# P18_CONNECT_DDR1.net
KiCad netlist of a schematic drawn in Altium Designer
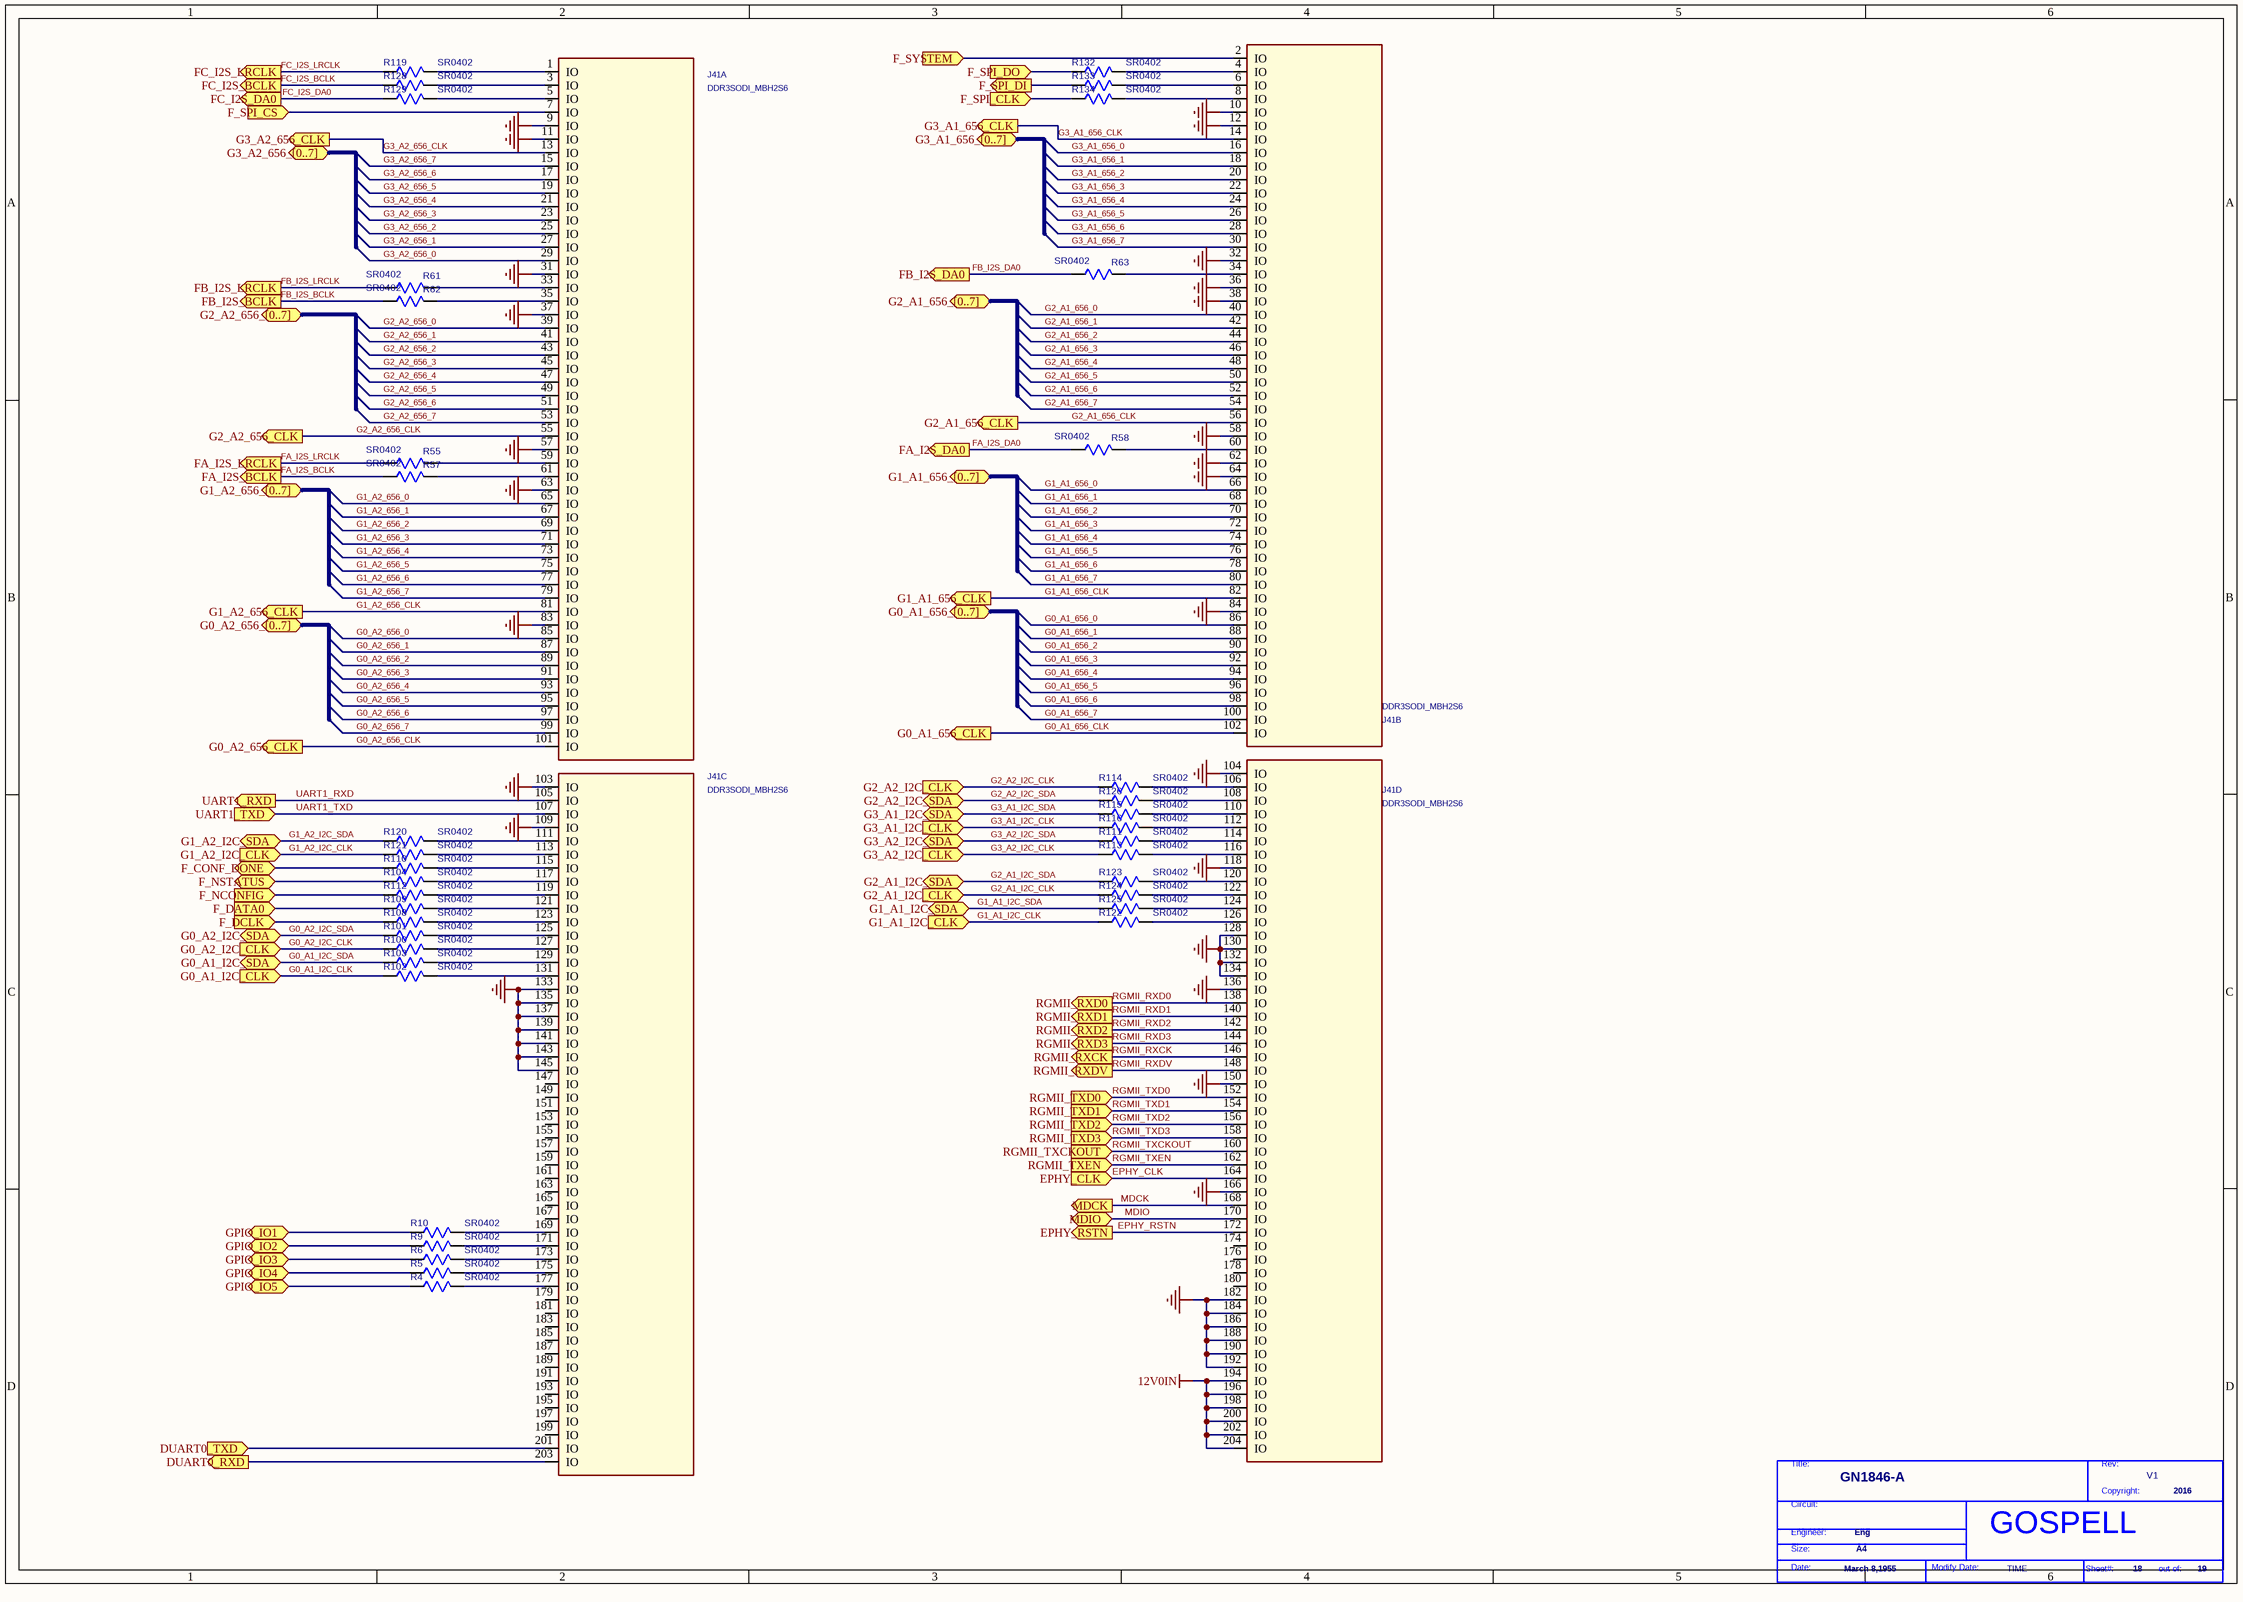
[diagram p0: P18 CONNECT DDR1.SchDoc]

(export (version "E")
  (design (tool "Eeschema 10.0.6"))
  (components
    (comp (ref "J41") (value "DDR3SODI_MBH2S6") (libsource (lib "*") (part "DDRSD_MB")))
    (comp (ref "R4") (value "SR0402") (libsource (lib "*") (part "R_1")))
    (comp (ref "R5") (value "SR0402") (libsource (lib "*") (part "R_1")))
    (comp (ref "R6") (value "SR0402") (libsource (lib "*") (part "R_1")))
    (comp (ref "R9") (value "SR0402") (libsource (lib "*") (part "R_1")))
    (comp (ref "R10") (value "SR0402") (libsource (lib "*") (part "R_1")))
    (comp (ref "R55") (value "SR0402") (libsource (lib "*") (part "R_1")))
    (comp (ref "R57") (value "SR0402") (libsource (lib "*") (part "R_1")))
    (comp (ref "R58") (value "SR0402") (libsource (lib "*") (part "R_1")))
    (comp (ref "R61") (value "SR0402") (libsource (lib "*") (part "R_1")))
    (comp (ref "R62") (value "SR0402") (libsource (lib "*") (part "R_1")))
    (comp (ref "R63") (value "SR0402") (libsource (lib "*") (part "R_1")))
    (comp (ref "R100") (value "SR0402") (libsource (lib "*") (part "R_1")))
    (comp (ref "R101") (value "SR0402") (libsource (lib "*") (part "R_1")))
    (comp (ref "R102") (value "SR0402") (libsource (lib "*") (part "R_1")))
    (comp (ref "R103") (value "SR0402") (libsource (lib "*") (part "R_1")))
    (comp (ref "R104") (value "SR0402") (libsource (lib "*") (part "R_1")))
    (comp (ref "R108") (value "SR0402") (libsource (lib "*") (part "R_1")))
    (comp (ref "R109") (value "SR0402") (libsource (lib "*") (part "R_1")))
    (comp (ref "R110") (value "SR0402") (libsource (lib "*") (part "R_1")))
    (comp (ref "R111") (value "SR0402") (libsource (lib "*") (part "R_1")))
    (comp (ref "R112") (value "SR0402") (libsource (lib "*") (part "R_1")))
    (comp (ref "R113") (value "SR0402") (libsource (lib "*") (part "R_1")))
    (comp (ref "R114") (value "SR0402") (libsource (lib "*") (part "R_1")))
    (comp (ref "R115") (value "SR0402") (libsource (lib "*") (part "R_1")))
    (comp (ref "R116") (value "SR0402") (libsource (lib "*") (part "R_1")))
    (comp (ref "R119") (value "SR0402") (libsource (lib "*") (part "R_1")))
    (comp (ref "R120") (value "SR0402") (libsource (lib "*") (part "R_1")))
    (comp (ref "R121") (value "SR0402") (libsource (lib "*") (part "R_1")))
    (comp (ref "R122") (value "SR0402") (libsource (lib "*") (part "R_1")))
    (comp (ref "R123") (value "SR0402") (libsource (lib "*") (part "R_1")))
    (comp (ref "R124") (value "SR0402") (libsource (lib "*") (part "R_1")))
    (comp (ref "R125") (value "SR0402") (libsource (lib "*") (part "R_1")))
    (comp (ref "R126") (value "SR0402") (libsource (lib "*") (part "R_1")))
    (comp (ref "R128") (value "SR0402") (libsource (lib "*") (part "R_1")))
    (comp (ref "R129") (value "SR0402") (libsource (lib "*") (part "R_1")))
    (comp (ref "R132") (value "SR0402") (libsource (lib "*") (part "R_1")))
    (comp (ref "R133") (value "SR0402") (libsource (lib "*") (part "R_1")))
    (comp (ref "R134") (value "SR0402") (libsource (lib "*") (part "R_1")))
  )
  (nets
    (net (code "1") (name "/DUART0_RXD") (class "Default")
      (node (ref "J41") (pin "203") (pinfunction "IO_203") (pintype "passive"))
    )
    (net (code "2") (name "/DUART0_TXD") (class "Default")
      (node (ref "J41") (pin "201") (pinfunction "IO_201") (pintype "passive"))
    )
    (net (code "3") (name "/EPHY_CLK") (class "Default")
      (node (ref "J41") (pin "164") (pinfunction "IO_164") (pintype "passive"))
    )
    (net (code "4") (name "/EPHY_RSTN") (class "Default")
      (node (ref "J41") (pin "172") (pinfunction "IO_172") (pintype "passive"))
    )
    (net (code "5") (name "/FA_I2S_BCLK") (class "Default")
      (node (ref "R57") (pin "2") (pinfunction "B_2") (pintype "passive"))
    )
    (net (code "6") (name "/FA_I2S_DA0") (class "Default")
      (node (ref "R58") (pin "2") (pinfunction "B_2") (pintype "passive"))
    )
    (net (code "7") (name "/FA_I2S_LRCLK") (class "Default")
      (node (ref "R55") (pin "2") (pinfunction "B_2") (pintype "passive"))
    )
    (net (code "8") (name "/FB_I2S_BCLK") (class "Default")
      (node (ref "R62") (pin "2") (pinfunction "B_2") (pintype "passive"))
    )
    (net (code "9") (name "/FB_I2S_DA0") (class "Default")
      (node (ref "R63") (pin "2") (pinfunction "B_2") (pintype "passive"))
    )
    (net (code "10") (name "/FB_I2S_LRCLK") (class "Default")
      (node (ref "R61") (pin "2") (pinfunction "B_2") (pintype "passive"))
    )
    (net (code "11") (name "/FC_I2S_BCLK") (class "Default")
      (node (ref "R128") (pin "1") (pinfunction "A_1") (pintype "passive"))
    )
    (net (code "12") (name "/FC_I2S_DA0") (class "Default")
      (node (ref "R129") (pin "1") (pinfunction "A_1") (pintype "passive"))
    )
    (net (code "13") (name "/FC_I2S_LRCLK") (class "Default")
      (node (ref "R119") (pin "1") (pinfunction "A_1") (pintype "passive"))
    )
    (net (code "14") (name "/F_CONF_DONE") (class "Default")
      (node (ref "R110") (pin "1") (pinfunction "A_1") (pintype "passive"))
    )
    (net (code "15") (name "/F_DATA0") (class "Default")
      (node (ref "R109") (pin "1") (pinfunction "A_1") (pintype "passive"))
    )
    (net (code "16") (name "/F_DCLK") (class "Default")
      (node (ref "R108") (pin "1") (pinfunction "A_1") (pintype "passive"))
    )
    (net (code "17") (name "/F_NCONFIG") (class "Default")
      (node (ref "R112") (pin "1") (pinfunction "A_1") (pintype "passive"))
    )
    (net (code "18") (name "/F_NSTATUS") (class "Default")
      (node (ref "R104") (pin "1") (pinfunction "A_1") (pintype "passive"))
    )
    (net (code "19") (name "/F_SPI_CLK") (class "Default")
      (node (ref "R134") (pin "1") (pinfunction "A_1") (pintype "passive"))
    )
    (net (code "20") (name "/F_SPI_CS") (class "Default")
      (node (ref "J41") (pin "7") (pinfunction "IO_7") (pintype "passive"))
    )
    (net (code "21") (name "/F_SPI_DI") (class "Default")
      (node (ref "R133") (pin "1") (pinfunction "A_1") (pintype "passive"))
    )
    (net (code "22") (name "/F_SPI_DO") (class "Default")
      (node (ref "R132") (pin "1") (pinfunction "A_1") (pintype "passive"))
    )
    (net (code "23") (name "/F_SYSTEM") (class "Default")
      (node (ref "J41") (pin "2") (pinfunction "IO_2") (pintype "passive"))
    )
    (net (code "24") (name "/G0_A1_656_0") (class "Default")
      (node (ref "J41") (pin "86") (pinfunction "IO_86") (pintype "passive"))
    )
    (net (code "25") (name "/G0_A1_656_1") (class "Default")
      (node (ref "J41") (pin "88") (pinfunction "IO_88") (pintype "passive"))
    )
    (net (code "26") (name "/G0_A1_656_2") (class "Default")
      (node (ref "J41") (pin "90") (pinfunction "IO_90") (pintype "passive"))
    )
    (net (code "27") (name "/G0_A1_656_3") (class "Default")
      (node (ref "J41") (pin "92") (pinfunction "IO_92") (pintype "passive"))
    )
    (net (code "28") (name "/G0_A1_656_4") (class "Default")
      (node (ref "J41") (pin "94") (pinfunction "IO_94") (pintype "passive"))
    )
    (net (code "29") (name "/G0_A1_656_5") (class "Default")
      (node (ref "J41") (pin "96") (pinfunction "IO_96") (pintype "passive"))
    )
    (net (code "30") (name "/G0_A1_656_6") (class "Default")
      (node (ref "J41") (pin "98") (pinfunction "IO_98") (pintype "passive"))
    )
    (net (code "31") (name "/G0_A1_656_7") (class "Default")
      (node (ref "J41") (pin "100") (pinfunction "IO_100") (pintype "passive"))
    )
    (net (code "32") (name "/G0_A1_656_CLK") (class "Default")
      (node (ref "J41") (pin "102") (pinfunction "IO_102") (pintype "passive"))
    )
    (net (code "34") (name "/G0_A1_I2C_CLK") (class "Default")
      (node (ref "R102") (pin "1") (pinfunction "A_1") (pintype "passive"))
    )
    (net (code "35") (name "/G0_A1_I2C_SDA") (class "Default")
      (node (ref "R103") (pin "1") (pinfunction "A_1") (pintype "passive"))
    )
    (net (code "36") (name "/G0_A2_656_0") (class "Default")
      (node (ref "J41") (pin "85") (pinfunction "IO_85") (pintype "passive"))
    )
    (net (code "37") (name "/G0_A2_656_1") (class "Default")
      (node (ref "J41") (pin "87") (pinfunction "IO_87") (pintype "passive"))
    )
    (net (code "38") (name "/G0_A2_656_2") (class "Default")
      (node (ref "J41") (pin "89") (pinfunction "IO_89") (pintype "passive"))
    )
    (net (code "39") (name "/G0_A2_656_3") (class "Default")
      (node (ref "J41") (pin "91") (pinfunction "IO_91") (pintype "passive"))
    )
    (net (code "40") (name "/G0_A2_656_4") (class "Default")
      (node (ref "J41") (pin "93") (pinfunction "IO_93") (pintype "passive"))
    )
    (net (code "41") (name "/G0_A2_656_5") (class "Default")
      (node (ref "J41") (pin "95") (pinfunction "IO_95") (pintype "passive"))
    )
    (net (code "42") (name "/G0_A2_656_6") (class "Default")
      (node (ref "J41") (pin "97") (pinfunction "IO_97") (pintype "passive"))
    )
    (net (code "43") (name "/G0_A2_656_7") (class "Default")
      (node (ref "J41") (pin "99") (pinfunction "IO_99") (pintype "passive"))
    )
    (net (code "44") (name "/G0_A2_656_CLK") (class "Default")
      (node (ref "J41") (pin "101") (pinfunction "IO_101") (pintype "passive"))
    )
    (net (code "46") (name "/G0_A2_I2C_CLK") (class "Default")
      (node (ref "R100") (pin "1") (pinfunction "A_1") (pintype "passive"))
    )
    (net (code "47") (name "/G0_A2_I2C_SDA") (class "Default")
      (node (ref "R101") (pin "1") (pinfunction "A_1") (pintype "passive"))
    )
    (net (code "48") (name "/G1_A1_656_0") (class "Default")
      (node (ref "J41") (pin "66") (pinfunction "IO_66") (pintype "passive"))
    )
    (net (code "49") (name "/G1_A1_656_1") (class "Default")
      (node (ref "J41") (pin "68") (pinfunction "IO_68") (pintype "passive"))
    )
    (net (code "50") (name "/G1_A1_656_2") (class "Default")
      (node (ref "J41") (pin "70") (pinfunction "IO_70") (pintype "passive"))
    )
    (net (code "51") (name "/G1_A1_656_3") (class "Default")
      (node (ref "J41") (pin "72") (pinfunction "IO_72") (pintype "passive"))
    )
    (net (code "52") (name "/G1_A1_656_4") (class "Default")
      (node (ref "J41") (pin "74") (pinfunction "IO_74") (pintype "passive"))
    )
    (net (code "53") (name "/G1_A1_656_5") (class "Default")
      (node (ref "J41") (pin "76") (pinfunction "IO_76") (pintype "passive"))
    )
    (net (code "54") (name "/G1_A1_656_6") (class "Default")
      (node (ref "J41") (pin "78") (pinfunction "IO_78") (pintype "passive"))
    )
    (net (code "55") (name "/G1_A1_656_7") (class "Default")
      (node (ref "J41") (pin "80") (pinfunction "IO_80") (pintype "passive"))
    )
    (net (code "56") (name "/G1_A1_656_CLK") (class "Default")
      (node (ref "J41") (pin "82") (pinfunction "IO_82") (pintype "passive"))
    )
    (net (code "58") (name "/G1_A1_I2C_CLK") (class "Default")
      (node (ref "R122") (pin "1") (pinfunction "A_1") (pintype "passive"))
    )
    (net (code "59") (name "/G1_A1_I2C_SDA") (class "Default")
      (node (ref "R125") (pin "1") (pinfunction "A_1") (pintype "passive"))
    )
    (net (code "60") (name "/G1_A2_656_0") (class "Default")
      (node (ref "J41") (pin "65") (pinfunction "IO_65") (pintype "passive"))
    )
    (net (code "61") (name "/G1_A2_656_1") (class "Default")
      (node (ref "J41") (pin "67") (pinfunction "IO_67") (pintype "passive"))
    )
    (net (code "62") (name "/G1_A2_656_2") (class "Default")
      (node (ref "J41") (pin "69") (pinfunction "IO_69") (pintype "passive"))
    )
    (net (code "63") (name "/G1_A2_656_3") (class "Default")
      (node (ref "J41") (pin "71") (pinfunction "IO_71") (pintype "passive"))
    )
    (net (code "64") (name "/G1_A2_656_4") (class "Default")
      (node (ref "J41") (pin "73") (pinfunction "IO_73") (pintype "passive"))
    )
    (net (code "65") (name "/G1_A2_656_5") (class "Default")
      (node (ref "J41") (pin "75") (pinfunction "IO_75") (pintype "passive"))
    )
    (net (code "66") (name "/G1_A2_656_6") (class "Default")
      (node (ref "J41") (pin "77") (pinfunction "IO_77") (pintype "passive"))
    )
    (net (code "67") (name "/G1_A2_656_7") (class "Default")
      (node (ref "J41") (pin "79") (pinfunction "IO_79") (pintype "passive"))
    )
    (net (code "68") (name "/G1_A2_656_CLK") (class "Default")
      (node (ref "J41") (pin "81") (pinfunction "IO_81") (pintype "passive"))
    )
    (net (code "70") (name "/G1_A2_I2C_CLK") (class "Default")
      (node (ref "R121") (pin "1") (pinfunction "A_1") (pintype "passive"))
    )
    (net (code "71") (name "/G1_A2_I2C_SDA") (class "Default")
      (node (ref "R120") (pin "1") (pinfunction "A_1") (pintype "passive"))
    )
    (net (code "72") (name "/G2_A1_656_0") (class "Default")
      (node (ref "J41") (pin "40") (pinfunction "IO_40") (pintype "passive"))
    )
    (net (code "73") (name "/G2_A1_656_1") (class "Default")
      (node (ref "J41") (pin "42") (pinfunction "IO_42") (pintype "passive"))
    )
    (net (code "74") (name "/G2_A1_656_2") (class "Default")
      (node (ref "J41") (pin "44") (pinfunction "IO_44") (pintype "passive"))
    )
    (net (code "75") (name "/G2_A1_656_3") (class "Default")
      (node (ref "J41") (pin "46") (pinfunction "IO_46") (pintype "passive"))
    )
    (net (code "76") (name "/G2_A1_656_4") (class "Default")
      (node (ref "J41") (pin "48") (pinfunction "IO_48") (pintype "passive"))
    )
    (net (code "77") (name "/G2_A1_656_5") (class "Default")
      (node (ref "J41") (pin "50") (pinfunction "IO_50") (pintype "passive"))
    )
    (net (code "78") (name "/G2_A1_656_6") (class "Default")
      (node (ref "J41") (pin "52") (pinfunction "IO_52") (pintype "passive"))
    )
    (net (code "79") (name "/G2_A1_656_7") (class "Default")
      (node (ref "J41") (pin "54") (pinfunction "IO_54") (pintype "passive"))
    )
    (net (code "80") (name "/G2_A1_656_CLK") (class "Default")
      (node (ref "J41") (pin "56") (pinfunction "IO_56") (pintype "passive"))
    )
    (net (code "82") (name "/G2_A1_I2C_CLK") (class "Default")
      (node (ref "R124") (pin "1") (pinfunction "A_1") (pintype "passive"))
    )
    (net (code "83") (name "/G2_A1_I2C_SDA") (class "Default")
      (node (ref "R123") (pin "1") (pinfunction "A_1") (pintype "passive"))
    )
    (net (code "84") (name "/G2_A2_656_0") (class "Default")
      (node (ref "J41") (pin "39") (pinfunction "IO_39") (pintype "passive"))
    )
    (net (code "85") (name "/G2_A2_656_1") (class "Default")
      (node (ref "J41") (pin "41") (pinfunction "IO_41") (pintype "passive"))
    )
    (net (code "86") (name "/G2_A2_656_2") (class "Default")
      (node (ref "J41") (pin "43") (pinfunction "IO_43") (pintype "passive"))
    )
    (net (code "87") (name "/G2_A2_656_3") (class "Default")
      (node (ref "J41") (pin "45") (pinfunction "IO_45") (pintype "passive"))
    )
    (net (code "88") (name "/G2_A2_656_4") (class "Default")
      (node (ref "J41") (pin "47") (pinfunction "IO_47") (pintype "passive"))
    )
    (net (code "89") (name "/G2_A2_656_5") (class "Default")
      (node (ref "J41") (pin "49") (pinfunction "IO_49") (pintype "passive"))
    )
    (net (code "90") (name "/G2_A2_656_6") (class "Default")
      (node (ref "J41") (pin "51") (pinfunction "IO_51") (pintype "passive"))
    )
    (net (code "91") (name "/G2_A2_656_7") (class "Default")
      (node (ref "J41") (pin "53") (pinfunction "IO_53") (pintype "passive"))
    )
    (net (code "92") (name "/G2_A2_656_CLK") (class "Default")
      (node (ref "J41") (pin "55") (pinfunction "IO_55") (pintype "passive"))
    )
    (net (code "94") (name "/G2_A2_I2C_CLK") (class "Default")
      (node (ref "R114") (pin "1") (pinfunction "A_1") (pintype "passive"))
    )
    (net (code "95") (name "/G2_A2_I2C_SDA") (class "Default")
      (node (ref "R126") (pin "1") (pinfunction "A_1") (pintype "passive"))
    )
    (net (code "96") (name "/G3_A1_656_0") (class "Default")
      (node (ref "J41") (pin "16") (pinfunction "IO_16") (pintype "passive"))
    )
    (net (code "97") (name "/G3_A1_656_1") (class "Default")
      (node (ref "J41") (pin "18") (pinfunction "IO_18") (pintype "passive"))
    )
    (net (code "98") (name "/G3_A1_656_2") (class "Default")
      (node (ref "J41") (pin "20") (pinfunction "IO_20") (pintype "passive"))
    )
    (net (code "99") (name "/G3_A1_656_3") (class "Default")
      (node (ref "J41") (pin "22") (pinfunction "IO_22") (pintype "passive"))
    )
    (net (code "100") (name "/G3_A1_656_4") (class "Default")
      (node (ref "J41") (pin "24") (pinfunction "IO_24") (pintype "passive"))
    )
    (net (code "101") (name "/G3_A1_656_5") (class "Default")
      (node (ref "J41") (pin "26") (pinfunction "IO_26") (pintype "passive"))
    )
    (net (code "102") (name "/G3_A1_656_6") (class "Default")
      (node (ref "J41") (pin "28") (pinfunction "IO_28") (pintype "passive"))
    )
    (net (code "103") (name "/G3_A1_656_7") (class "Default")
      (node (ref "J41") (pin "30") (pinfunction "IO_30") (pintype "passive"))
    )
    (net (code "104") (name "/G3_A1_656_CLK") (class "Default")
      (node (ref "J41") (pin "14") (pinfunction "IO_14") (pintype "passive"))
    )
    (net (code "106") (name "/G3_A1_I2C_CLK") (class "Default")
      (node (ref "R116") (pin "1") (pinfunction "A_1") (pintype "passive"))
    )
    (net (code "107") (name "/G3_A1_I2C_SDA") (class "Default")
      (node (ref "R115") (pin "1") (pinfunction "A_1") (pintype "passive"))
    )
    (net (code "108") (name "/G3_A2_656_0") (class "Default")
      (node (ref "J41") (pin "29") (pinfunction "IO_29") (pintype "passive"))
    )
    (net (code "109") (name "/G3_A2_656_1") (class "Default")
      (node (ref "J41") (pin "27") (pinfunction "IO_27") (pintype "passive"))
    )
    (net (code "110") (name "/G3_A2_656_2") (class "Default")
      (node (ref "J41") (pin "25") (pinfunction "IO_25") (pintype "passive"))
    )
    (net (code "111") (name "/G3_A2_656_3") (class "Default")
      (node (ref "J41") (pin "23") (pinfunction "IO_23") (pintype "passive"))
    )
    (net (code "112") (name "/G3_A2_656_4") (class "Default")
      (node (ref "J41") (pin "21") (pinfunction "IO_21") (pintype "passive"))
    )
    (net (code "113") (name "/G3_A2_656_5") (class "Default")
      (node (ref "J41") (pin "19") (pinfunction "IO_19") (pintype "passive"))
    )
    (net (code "114") (name "/G3_A2_656_6") (class "Default")
      (node (ref "J41") (pin "17") (pinfunction "IO_17") (pintype "passive"))
    )
    (net (code "115") (name "/G3_A2_656_7") (class "Default")
      (node (ref "J41") (pin "15") (pinfunction "IO_15") (pintype "passive"))
    )
    (net (code "116") (name "/G3_A2_656_CLK") (class "Default")
      (node (ref "J41") (pin "13") (pinfunction "IO_13") (pintype "passive"))
    )
    (net (code "118") (name "/G3_A2_I2C_CLK") (class "Default")
      (node (ref "R113") (pin "1") (pinfunction "A_1") (pintype "passive"))
    )
    (net (code "119") (name "/G3_A2_I2C_SDA") (class "Default")
      (node (ref "R111") (pin "1") (pinfunction "A_1") (pintype "passive"))
    )
    (net (code "120") (name "/GPIO_IO1") (class "Default")
      (node (ref "R10") (pin "1") (pinfunction "A_1") (pintype "passive"))
    )
    (net (code "121") (name "/GPIO_IO2") (class "Default")
      (node (ref "R9") (pin "1") (pinfunction "A_1") (pintype "passive"))
    )
    (net (code "122") (name "/GPIO_IO3") (class "Default")
      (node (ref "R6") (pin "1") (pinfunction "A_1") (pintype "passive"))
    )
    (net (code "123") (name "/GPIO_IO4") (class "Default")
      (node (ref "R5") (pin "1") (pinfunction "A_1") (pintype "passive"))
    )
    (net (code "124") (name "/GPIO_IO5") (class "Default")
      (node (ref "R4") (pin "1") (pinfunction "A_1") (pintype "passive"))
    )
    (net (code "125") (name "/MDCK") (class "Default")
      (node (ref "J41") (pin "168") (pinfunction "IO_168") (pintype "passive"))
    )
    (net (code "126") (name "/MDIO") (class "Default")
      (node (ref "J41") (pin "170") (pinfunction "IO_170") (pintype "passive"))
    )
    (net (code "127") (name "/RGMII_RXCK") (class "Default")
      (node (ref "J41") (pin "146") (pinfunction "IO_146") (pintype "passive"))
    )
    (net (code "128") (name "/RGMII_RXD0") (class "Default")
      (node (ref "J41") (pin "138") (pinfunction "IO_138") (pintype "passive"))
    )
    (net (code "129") (name "/RGMII_RXD1") (class "Default")
      (node (ref "J41") (pin "140") (pinfunction "IO_140") (pintype "passive"))
    )
    (net (code "130") (name "/RGMII_RXD2") (class "Default")
      (node (ref "J41") (pin "142") (pinfunction "IO_142") (pintype "passive"))
    )
    (net (code "131") (name "/RGMII_RXD3") (class "Default")
      (node (ref "J41") (pin "144") (pinfunction "IO_144") (pintype "passive"))
    )
    (net (code "132") (name "/RGMII_RXDV") (class "Default")
      (node (ref "J41") (pin "148") (pinfunction "IO_148") (pintype "passive"))
    )
    (net (code "133") (name "/RGMII_TXCKOUT") (class "Default")
      (node (ref "J41") (pin "160") (pinfunction "IO_160") (pintype "passive"))
    )
    (net (code "134") (name "/RGMII_TXD0") (class "Default")
      (node (ref "J41") (pin "152") (pinfunction "IO_152") (pintype "passive"))
    )
    (net (code "135") (name "/RGMII_TXD1") (class "Default")
      (node (ref "J41") (pin "154") (pinfunction "IO_154") (pintype "passive"))
    )
    (net (code "136") (name "/RGMII_TXD2") (class "Default")
      (node (ref "J41") (pin "156") (pinfunction "IO_156") (pintype "passive"))
    )
    (net (code "137") (name "/RGMII_TXD3") (class "Default")
      (node (ref "J41") (pin "158") (pinfunction "IO_158") (pintype "passive"))
    )
    (net (code "138") (name "/RGMII_TXEN") (class "Default")
      (node (ref "J41") (pin "162") (pinfunction "IO_162") (pintype "passive"))
    )
    (net (code "139") (name "/UART1_RXD") (class "Default")
      (node (ref "J41") (pin "105") (pinfunction "IO_105") (pintype "passive"))
    )
    (net (code "140") (name "/UART1_TXD") (class "Default")
      (node (ref "J41") (pin "107") (pinfunction "IO_107") (pintype "passive"))
    )
    (net (code "141") (name "12V0IN") (class "Default")
      (node (ref "J41") (pin "194") (pinfunction "IO_194") (pintype "passive"))
      (node (ref "J41") (pin "196") (pinfunction "IO_196") (pintype "passive"))
      (node (ref "J41") (pin "198") (pinfunction "IO_198") (pintype "passive"))
      (node (ref "J41") (pin "200") (pinfunction "IO_200") (pintype "passive"))
      (node (ref "J41") (pin "202") (pinfunction "IO_202") (pintype "passive"))
      (node (ref "J41") (pin "204") (pinfunction "IO_204") (pintype "passive"))
    )
    (net (code "142") (name "GND") (class "Default")
      (node (ref "J41") (pin "10") (pinfunction "IO_10") (pintype "passive"))
      (node (ref "J41") (pin "103") (pinfunction "IO_103") (pintype "passive"))
      (node (ref "J41") (pin "104") (pinfunction "IO_104") (pintype "passive"))
      (node (ref "J41") (pin "109") (pinfunction "IO_109") (pintype "passive"))
      (node (ref "J41") (pin "11") (pinfunction "IO_11") (pintype "passive"))
      (node (ref "J41") (pin "118") (pinfunction "IO_118") (pintype "passive"))
      (node (ref "J41") (pin "12") (pinfunction "IO_12") (pintype "passive"))
      (node (ref "J41") (pin "128") (pinfunction "IO_128") (pintype "passive"))
      (node (ref "J41") (pin "130") (pinfunction "IO_130") (pintype "passive"))
      (node (ref "J41") (pin "132") (pinfunction "IO_132") (pintype "passive"))
      (node (ref "J41") (pin "133") (pinfunction "IO_133") (pintype "passive"))
      (node (ref "J41") (pin "134") (pinfunction "IO_134") (pintype "passive"))
      (node (ref "J41") (pin "135") (pinfunction "IO_135") (pintype "passive"))
      (node (ref "J41") (pin "136") (pinfunction "IO_136") (pintype "passive"))
      (node (ref "J41") (pin "137") (pinfunction "IO_137") (pintype "passive"))
      (node (ref "J41") (pin "139") (pinfunction "IO_139") (pintype "passive"))
      (node (ref "J41") (pin "141") (pinfunction "IO_141") (pintype "passive"))
      (node (ref "J41") (pin "143") (pinfunction "IO_143") (pintype "passive"))
      (node (ref "J41") (pin "145") (pinfunction "IO_145") (pintype "passive"))
      (node (ref "J41") (pin "150") (pinfunction "IO_150") (pintype "passive"))
      (node (ref "J41") (pin "166") (pinfunction "IO_166") (pintype "passive"))
      (node (ref "J41") (pin "182") (pinfunction "IO_182") (pintype "passive"))
      (node (ref "J41") (pin "184") (pinfunction "IO_184") (pintype "passive"))
      (node (ref "J41") (pin "186") (pinfunction "IO_186") (pintype "passive"))
      (node (ref "J41") (pin "188") (pinfunction "IO_188") (pintype "passive"))
      (node (ref "J41") (pin "190") (pinfunction "IO_190") (pintype "passive"))
      (node (ref "J41") (pin "192") (pinfunction "IO_192") (pintype "passive"))
      (node (ref "J41") (pin "31") (pinfunction "IO_31") (pintype "passive"))
      (node (ref "J41") (pin "32") (pinfunction "IO_32") (pintype "passive"))
      (node (ref "J41") (pin "36") (pinfunction "IO_36") (pintype "passive"))
      (node (ref "J41") (pin "37") (pinfunction "IO_37") (pintype "passive"))
      (node (ref "J41") (pin "38") (pinfunction "IO_38") (pintype "passive"))
      (node (ref "J41") (pin "57") (pinfunction "IO_57") (pintype "passive"))
      (node (ref "J41") (pin "58") (pinfunction "IO_58") (pintype "passive"))
      (node (ref "J41") (pin "62") (pinfunction "IO_62") (pintype "passive"))
      (node (ref "J41") (pin "63") (pinfunction "IO_63") (pintype "passive"))
      (node (ref "J41") (pin "64") (pinfunction "IO_64") (pintype "passive"))
      (node (ref "J41") (pin "83") (pinfunction "IO_83") (pintype "passive"))
      (node (ref "J41") (pin "84") (pinfunction "IO_84") (pintype "passive"))
      (node (ref "J41") (pin "9") (pinfunction "IO_9") (pintype "passive"))
    )
    (net (code "143") (name "Net-(R4-B)") (class "Default")
      (node (ref "J41") (pin "177") (pinfunction "IO_177") (pintype "passive"))
      (node (ref "R4") (pin "2") (pinfunction "B_2") (pintype "passive"))
    )
    (net (code "144") (name "Net-(R5-B)") (class "Default")
      (node (ref "J41") (pin "175") (pinfunction "IO_175") (pintype "passive"))
      (node (ref "R5") (pin "2") (pinfunction "B_2") (pintype "passive"))
    )
    (net (code "145") (name "Net-(R6-B)") (class "Default")
      (node (ref "J41") (pin "173") (pinfunction "IO_173") (pintype "passive"))
      (node (ref "R6") (pin "2") (pinfunction "B_2") (pintype "passive"))
    )
    (net (code "146") (name "Net-(R9-B)") (class "Default")
      (node (ref "J41") (pin "171") (pinfunction "IO_171") (pintype "passive"))
      (node (ref "R9") (pin "2") (pinfunction "B_2") (pintype "passive"))
    )
    (net (code "147") (name "Net-(R10-B)") (class "Default")
      (node (ref "J41") (pin "169") (pinfunction "IO_169") (pintype "passive"))
      (node (ref "R10") (pin "2") (pinfunction "B_2") (pintype "passive"))
    )
    (net (code "148") (name "Net-(R55-A)") (class "Default")
      (node (ref "J41") (pin "59") (pinfunction "IO_59") (pintype "passive"))
      (node (ref "R55") (pin "1") (pinfunction "A_1") (pintype "passive"))
    )
    (net (code "149") (name "Net-(R57-A)") (class "Default")
      (node (ref "J41") (pin "61") (pinfunction "IO_61") (pintype "passive"))
      (node (ref "R57") (pin "1") (pinfunction "A_1") (pintype "passive"))
    )
    (net (code "150") (name "Net-(R58-A)") (class "Default")
      (node (ref "J41") (pin "60") (pinfunction "IO_60") (pintype "passive"))
      (node (ref "R58") (pin "1") (pinfunction "A_1") (pintype "passive"))
    )
    (net (code "151") (name "Net-(R61-A)") (class "Default")
      (node (ref "J41") (pin "33") (pinfunction "IO_33") (pintype "passive"))
      (node (ref "R61") (pin "1") (pinfunction "A_1") (pintype "passive"))
    )
    (net (code "152") (name "Net-(R62-A)") (class "Default")
      (node (ref "J41") (pin "35") (pinfunction "IO_35") (pintype "passive"))
      (node (ref "R62") (pin "1") (pinfunction "A_1") (pintype "passive"))
    )
    (net (code "153") (name "Net-(R63-A)") (class "Default")
      (node (ref "J41") (pin "34") (pinfunction "IO_34") (pintype "passive"))
      (node (ref "R63") (pin "1") (pinfunction "A_1") (pintype "passive"))
    )
    (net (code "154") (name "Net-(R100-B)") (class "Default")
      (node (ref "J41") (pin "127") (pinfunction "IO_127") (pintype "passive"))
      (node (ref "R100") (pin "2") (pinfunction "B_2") (pintype "passive"))
    )
    (net (code "155") (name "Net-(R101-B)") (class "Default")
      (node (ref "J41") (pin "125") (pinfunction "IO_125") (pintype "passive"))
      (node (ref "R101") (pin "2") (pinfunction "B_2") (pintype "passive"))
    )
    (net (code "156") (name "Net-(R102-B)") (class "Default")
      (node (ref "J41") (pin "131") (pinfunction "IO_131") (pintype "passive"))
      (node (ref "R102") (pin "2") (pinfunction "B_2") (pintype "passive"))
    )
    (net (code "157") (name "Net-(R103-B)") (class "Default")
      (node (ref "J41") (pin "129") (pinfunction "IO_129") (pintype "passive"))
      (node (ref "R103") (pin "2") (pinfunction "B_2") (pintype "passive"))
    )
    (net (code "158") (name "Net-(R104-B)") (class "Default")
      (node (ref "J41") (pin "117") (pinfunction "IO_117") (pintype "passive"))
      (node (ref "R104") (pin "2") (pinfunction "B_2") (pintype "passive"))
    )
    (net (code "159") (name "Net-(R108-B)") (class "Default")
      (node (ref "J41") (pin "123") (pinfunction "IO_123") (pintype "passive"))
      (node (ref "R108") (pin "2") (pinfunction "B_2") (pintype "passive"))
    )
    (net (code "160") (name "Net-(R109-B)") (class "Default")
      (node (ref "J41") (pin "121") (pinfunction "IO_121") (pintype "passive"))
      (node (ref "R109") (pin "2") (pinfunction "B_2") (pintype "passive"))
    )
    (net (code "161") (name "Net-(R110-B)") (class "Default")
      (node (ref "J41") (pin "115") (pinfunction "IO_115") (pintype "passive"))
      (node (ref "R110") (pin "2") (pinfunction "B_2") (pintype "passive"))
    )
    (net (code "162") (name "Net-(R111-B)") (class "Default")
      (node (ref "J41") (pin "114") (pinfunction "IO_114") (pintype "passive"))
      (node (ref "R111") (pin "2") (pinfunction "B_2") (pintype "passive"))
    )
    (net (code "163") (name "Net-(R112-B)") (class "Default")
      (node (ref "J41") (pin "119") (pinfunction "IO_119") (pintype "passive"))
      (node (ref "R112") (pin "2") (pinfunction "B_2") (pintype "passive"))
    )
    (net (code "164") (name "Net-(R113-B)") (class "Default")
      (node (ref "J41") (pin "116") (pinfunction "IO_116") (pintype "passive"))
      (node (ref "R113") (pin "2") (pinfunction "B_2") (pintype "passive"))
    )
    (net (code "165") (name "Net-(R114-B)") (class "Default")
      (node (ref "J41") (pin "106") (pinfunction "IO_106") (pintype "passive"))
      (node (ref "R114") (pin "2") (pinfunction "B_2") (pintype "passive"))
    )
    (net (code "166") (name "Net-(R115-B)") (class "Default")
      (node (ref "J41") (pin "110") (pinfunction "IO_110") (pintype "passive"))
      (node (ref "R115") (pin "2") (pinfunction "B_2") (pintype "passive"))
    )
    (net (code "167") (name "Net-(R116-B)") (class "Default")
      (node (ref "J41") (pin "112") (pinfunction "IO_112") (pintype "passive"))
      (node (ref "R116") (pin "2") (pinfunction "B_2") (pintype "passive"))
    )
    (net (code "168") (name "Net-(R119-B)") (class "Default")
      (node (ref "J41") (pin "1") (pinfunction "IO_1") (pintype "passive"))
      (node (ref "R119") (pin "2") (pinfunction "B_2") (pintype "passive"))
    )
    (net (code "169") (name "Net-(R120-B)") (class "Default")
      (node (ref "J41") (pin "111") (pinfunction "IO_111") (pintype "passive"))
      (node (ref "R120") (pin "2") (pinfunction "B_2") (pintype "passive"))
    )
    (net (code "170") (name "Net-(R121-B)") (class "Default")
      (node (ref "J41") (pin "113") (pinfunction "IO_113") (pintype "passive"))
      (node (ref "R121") (pin "2") (pinfunction "B_2") (pintype "passive"))
    )
    (net (code "171") (name "Net-(R122-B)") (class "Default")
      (node (ref "J41") (pin "126") (pinfunction "IO_126") (pintype "passive"))
      (node (ref "R122") (pin "2") (pinfunction "B_2") (pintype "passive"))
    )
    (net (code "172") (name "Net-(R123-B)") (class "Default")
      (node (ref "J41") (pin "120") (pinfunction "IO_120") (pintype "passive"))
      (node (ref "R123") (pin "2") (pinfunction "B_2") (pintype "passive"))
    )
    (net (code "173") (name "Net-(R124-B)") (class "Default")
      (node (ref "J41") (pin "122") (pinfunction "IO_122") (pintype "passive"))
      (node (ref "R124") (pin "2") (pinfunction "B_2") (pintype "passive"))
    )
    (net (code "174") (name "Net-(R125-B)") (class "Default")
      (node (ref "J41") (pin "124") (pinfunction "IO_124") (pintype "passive"))
      (node (ref "R125") (pin "2") (pinfunction "B_2") (pintype "passive"))
    )
    (net (code "175") (name "Net-(R126-B)") (class "Default")
      (node (ref "J41") (pin "108") (pinfunction "IO_108") (pintype "passive"))
      (node (ref "R126") (pin "2") (pinfunction "B_2") (pintype "passive"))
    )
    (net (code "176") (name "Net-(R128-B)") (class "Default")
      (node (ref "J41") (pin "3") (pinfunction "IO_3") (pintype "passive"))
      (node (ref "R128") (pin "2") (pinfunction "B_2") (pintype "passive"))
    )
    (net (code "177") (name "Net-(R129-B)") (class "Default")
      (node (ref "J41") (pin "5") (pinfunction "IO_5") (pintype "passive"))
      (node (ref "R129") (pin "2") (pinfunction "B_2") (pintype "passive"))
    )
    (net (code "178") (name "Net-(R132-B)") (class "Default")
      (node (ref "J41") (pin "4") (pinfunction "IO_4") (pintype "passive"))
      (node (ref "R132") (pin "2") (pinfunction "B_2") (pintype "passive"))
    )
    (net (code "179") (name "Net-(R133-B)") (class "Default")
      (node (ref "J41") (pin "6") (pinfunction "IO_6") (pintype "passive"))
      (node (ref "R133") (pin "2") (pinfunction "B_2") (pintype "passive"))
    )
    (net (code "180") (name "Net-(R134-B)") (class "Default")
      (node (ref "J41") (pin "8") (pinfunction "IO_8") (pintype "passive"))
      (node (ref "R134") (pin "2") (pinfunction "B_2") (pintype "passive"))
    )
    (net (code "181") (name "unconnected-(J41C-IO-Pad147)") (class "Default")
      (node (ref "J41") (pin "147") (pinfunction "IO_147") (pintype "passive"))
    )
    (net (code "182") (name "unconnected-(J41C-IO-Pad149)") (class "Default")
      (node (ref "J41") (pin "149") (pinfunction "IO_149") (pintype "passive"))
    )
    (net (code "183") (name "unconnected-(J41C-IO-Pad151)") (class "Default")
      (node (ref "J41") (pin "151") (pinfunction "IO_151") (pintype "passive"))
    )
    (net (code "184") (name "unconnected-(J41C-IO-Pad153)") (class "Default")
      (node (ref "J41") (pin "153") (pinfunction "IO_153") (pintype "passive"))
    )
    (net (code "185") (name "unconnected-(J41C-IO-Pad155)") (class "Default")
      (node (ref "J41") (pin "155") (pinfunction "IO_155") (pintype "passive"))
    )
    (net (code "186") (name "unconnected-(J41C-IO-Pad157)") (class "Default")
      (node (ref "J41") (pin "157") (pinfunction "IO_157") (pintype "passive"))
    )
    (net (code "187") (name "unconnected-(J41C-IO-Pad159)") (class "Default")
      (node (ref "J41") (pin "159") (pinfunction "IO_159") (pintype "passive"))
    )
    (net (code "188") (name "unconnected-(J41C-IO-Pad161)") (class "Default")
      (node (ref "J41") (pin "161") (pinfunction "IO_161") (pintype "passive"))
    )
    (net (code "189") (name "unconnected-(J41C-IO-Pad163)") (class "Default")
      (node (ref "J41") (pin "163") (pinfunction "IO_163") (pintype "passive"))
    )
    (net (code "190") (name "unconnected-(J41C-IO-Pad165)") (class "Default")
      (node (ref "J41") (pin "165") (pinfunction "IO_165") (pintype "passive"))
    )
    (net (code "191") (name "unconnected-(J41C-IO-Pad167)") (class "Default")
      (node (ref "J41") (pin "167") (pinfunction "IO_167") (pintype "passive"))
    )
    (net (code "192") (name "unconnected-(J41C-IO-Pad179)") (class "Default")
      (node (ref "J41") (pin "179") (pinfunction "IO_179") (pintype "passive"))
    )
    (net (code "193") (name "unconnected-(J41C-IO-Pad181)") (class "Default")
      (node (ref "J41") (pin "181") (pinfunction "IO_181") (pintype "passive"))
    )
    (net (code "194") (name "unconnected-(J41C-IO-Pad183)") (class "Default")
      (node (ref "J41") (pin "183") (pinfunction "IO_183") (pintype "passive"))
    )
    (net (code "195") (name "unconnected-(J41C-IO-Pad185)") (class "Default")
      (node (ref "J41") (pin "185") (pinfunction "IO_185") (pintype "passive"))
    )
    (net (code "196") (name "unconnected-(J41C-IO-Pad187)") (class "Default")
      (node (ref "J41") (pin "187") (pinfunction "IO_187") (pintype "passive"))
    )
    (net (code "197") (name "unconnected-(J41C-IO-Pad189)") (class "Default")
      (node (ref "J41") (pin "189") (pinfunction "IO_189") (pintype "passive"))
    )
    (net (code "198") (name "unconnected-(J41C-IO-Pad191)") (class "Default")
      (node (ref "J41") (pin "191") (pinfunction "IO_191") (pintype "passive"))
    )
    (net (code "199") (name "unconnected-(J41C-IO-Pad193)") (class "Default")
      (node (ref "J41") (pin "193") (pinfunction "IO_193") (pintype "passive"))
    )
    (net (code "200") (name "unconnected-(J41C-IO-Pad195)") (class "Default")
      (node (ref "J41") (pin "195") (pinfunction "IO_195") (pintype "passive"))
    )
    (net (code "201") (name "unconnected-(J41C-IO-Pad197)") (class "Default")
      (node (ref "J41") (pin "197") (pinfunction "IO_197") (pintype "passive"))
    )
    (net (code "202") (name "unconnected-(J41C-IO-Pad199)") (class "Default")
      (node (ref "J41") (pin "199") (pinfunction "IO_199") (pintype "passive"))
    )
    (net (code "203") (name "unconnected-(J41D-IO-Pad174)") (class "Default")
      (node (ref "J41") (pin "174") (pinfunction "IO_174") (pintype "passive"))
    )
    (net (code "204") (name "unconnected-(J41D-IO-Pad176)") (class "Default")
      (node (ref "J41") (pin "176") (pinfunction "IO_176") (pintype "passive"))
    )
    (net (code "205") (name "unconnected-(J41D-IO-Pad178)") (class "Default")
      (node (ref "J41") (pin "178") (pinfunction "IO_178") (pintype "passive"))
    )
    (net (code "206") (name "unconnected-(J41D-IO-Pad180)") (class "Default")
      (node (ref "J41") (pin "180") (pinfunction "IO_180") (pintype "passive"))
    )
  )
)
